# ADC.net
KiCad netlist of a schematic drawn in EAGLE
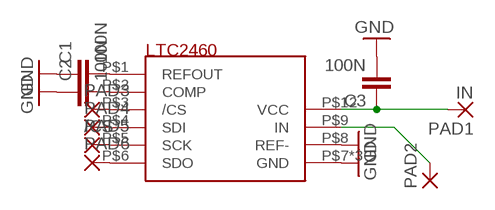
[diagram p0: schematic, sheet 1]

(export (version "E")
  (design (tool "Eeschema 10.0.6"))
  (components
    (comp (ref "C1")
      (value "100N")
      (footprint "eagle-import:C0805")
      (libsource (lib "eagle-import") (part "C-EUC0805"))
    )
    (comp (ref "C2")
      (value "100N")
      (footprint "eagle-import:C0805")
      (libsource (lib "eagle-import") (part "C-EUC0805"))
    )
    (comp (ref "C3")
      (value "100N")
      (footprint "eagle-import:C0805")
      (libsource (lib "eagle-import") (part "C-EUC0805"))
    )
    (comp (ref "PAD1")
      (value "IN")
      (footprint "eagle-import:2,54_0,8")
      (libsource (lib "eagle-import") (part "2,54/0,8"))
    )
    (comp (ref "PAD2")
      (value "2,54/0,8")
      (footprint "eagle-import:2,54_0,8")
      (libsource (lib "eagle-import") (part "2,54/0,8"))
    )
    (comp (ref "PAD3")
      (value "/CS")
      (footprint "eagle-import:2,54_0,8")
      (libsource (lib "eagle-import") (part "2,54/0,8"))
    )
    (comp (ref "PAD4")
      (value "2,54/0,8")
      (footprint "eagle-import:2,54_0,8")
      (libsource (lib "eagle-import") (part "2,54/0,8"))
    )
    (comp (ref "PAD5")
      (value "2,54/0,8")
      (footprint "eagle-import:2,54_0,8")
      (libsource (lib "eagle-import") (part "2,54/0,8"))
    )
    (comp (ref "PAD6")
      (value "2,54/0,8")
      (footprint "eagle-import:2,54_0,8")
      (libsource (lib "eagle-import") (part "2,54/0,8"))
    )
    (comp (ref "U$1")
      (value "LTC2460")
      (footprint "eagle-import:MSOP8_LT")
      (libsource (lib "eagle-import") (part "LTC2460"))
    )
  )
  (nets
    (net (code "1") (name "GND") (class "Default")
      (node (ref "C1") (pin "1") (pinfunction "1_1") (pintype "passive"))
      (node (ref "C2") (pin "1") (pinfunction "1_1") (pintype "passive"))
      (node (ref "C3") (pin "2") (pinfunction "2_2") (pintype "passive"))
      (node (ref "U$1") (pin "P$10") (pinfunction "GND_P$10") (pintype "bidirectional"))
      (node (ref "U$1") (pin "P$11") (pinfunction "GND_P$11") (pintype "bidirectional"))
      (node (ref "U$1") (pin "P$7") (pinfunction "GND_P$7") (pintype "bidirectional"))
      (node (ref "U$1") (pin "P$8") (pinfunction "REF-_P$8") (pintype "bidirectional"))
    )
    (net (code "2") (name "Net-(PAD1-P)") (class "Default")
      (node (ref "C3") (pin "1") (pinfunction "1_1") (pintype "passive"))
      (node (ref "PAD1") (pin "1") (pinfunction "P_1") (pintype "passive"))
      (node (ref "U$1") (pin "P$12") (pinfunction "VCC_P$12") (pintype "bidirectional"))
    )
    (net (code "3") (name "Net-(PAD2-P)") (class "Default")
      (node (ref "PAD2") (pin "1") (pinfunction "P_1") (pintype "passive"))
      (node (ref "U$1") (pin "P$9") (pinfunction "IN_P$9") (pintype "bidirectional"))
    )
    (net (code "4") (name "Net-(PAD3-P)") (class "Default")
      (node (ref "PAD3") (pin "1") (pinfunction "P_1") (pintype "passive"))
      (node (ref "U$1") (pin "P$3") (pinfunction "/CS_P$3") (pintype "bidirectional"))
    )
    (net (code "5") (name "Net-(PAD4-P)") (class "Default")
      (node (ref "PAD4") (pin "1") (pinfunction "P_1") (pintype "passive"))
      (node (ref "U$1") (pin "P$4") (pinfunction "SDI_P$4") (pintype "bidirectional"))
    )
    (net (code "6") (name "Net-(PAD5-P)") (class "Default")
      (node (ref "PAD5") (pin "1") (pinfunction "P_1") (pintype "passive"))
      (node (ref "U$1") (pin "P$5") (pinfunction "SCK_P$5") (pintype "bidirectional"))
    )
    (net (code "7") (name "Net-(PAD6-P)") (class "Default")
      (node (ref "PAD6") (pin "1") (pinfunction "P_1") (pintype "passive"))
      (node (ref "U$1") (pin "P$6") (pinfunction "SDO_P$6") (pintype "bidirectional"))
    )
    (net (code "8") (name "Net-(U$1-COMP)") (class "Default")
      (node (ref "C2") (pin "2") (pinfunction "2_2") (pintype "passive"))
      (node (ref "U$1") (pin "P$2") (pinfunction "COMP_P$2") (pintype "bidirectional"))
    )
    (net (code "9") (name "Net-(U$1-REFOUT)") (class "Default")
      (node (ref "C1") (pin "2") (pinfunction "2_2") (pintype "passive"))
      (node (ref "U$1") (pin "P$1") (pinfunction "REFOUT_P$1") (pintype "bidirectional"))
    )
  )
)
